# timer-LED.net
KiCad netlist of a schematic drawn in EAGLE
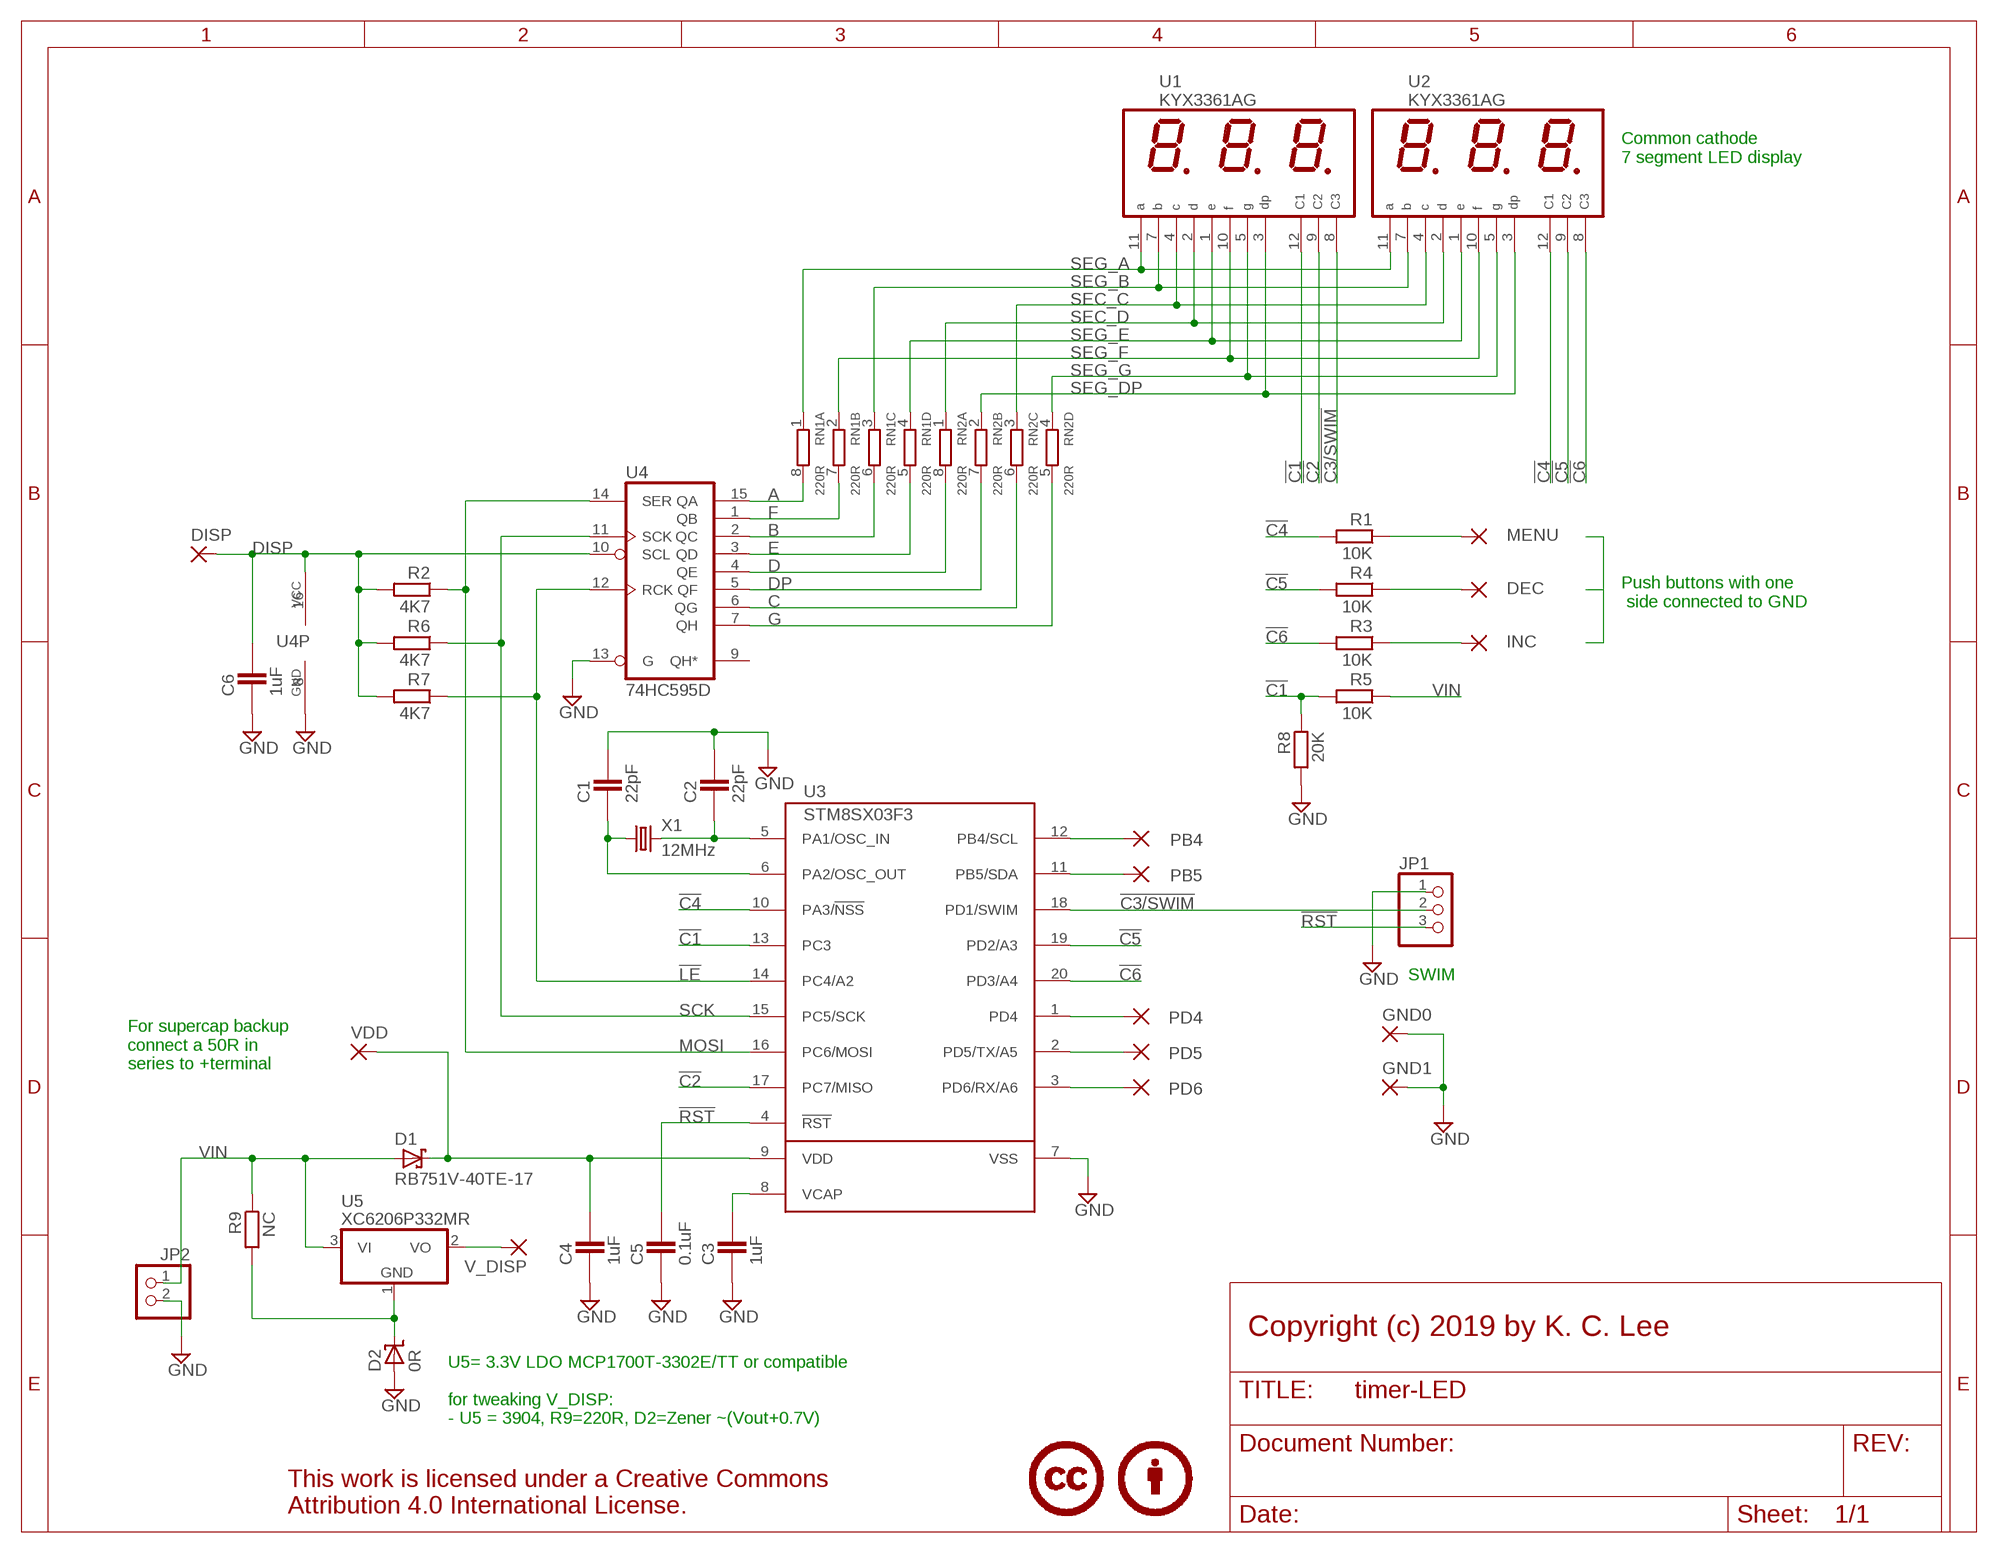
[diagram p0: schematic, sheet 1]

(export (version "E")
  (design (tool "Eeschema 10.0.6"))
  (components
    (comp (ref "C1")
      (value "22pF")
      (footprint "eagle-import:CAPC1608X92N")
      (libsource (lib "eagle-import") (part "CAPACITOR_0603"))
    )
    (comp (ref "C2")
      (value "22pF")
      (footprint "eagle-import:CAPC1608X92N")
      (libsource (lib "eagle-import") (part "CAPACITOR_0603"))
    )
    (comp (ref "C3")
      (value "1uF")
      (footprint "eagle-import:CAPC1608X92N")
      (libsource (lib "eagle-import") (part "CAPACITOR_0603"))
    )
    (comp (ref "C4")
      (value "1uF")
      (footprint "eagle-import:CAPC1608X92N")
      (libsource (lib "eagle-import") (part "CAPACITOR_0603"))
    )
    (comp (ref "C5")
      (value "0.1uF")
      (footprint "eagle-import:CAPC1608X92N")
      (libsource (lib "eagle-import") (part "CAPACITOR_0603"))
    )
    (comp (ref "C6")
      (value "1uF")
      (footprint "eagle-import:CAP2012X70N")
      (libsource (lib "eagle-import") (part "CAPACITOR_0805N"))
    )
    (comp (ref "D1")
      (value "RB751V-40TE-17")
      (footprint "eagle-import:SOD2514X100N")
      (libsource (lib "eagle-import") (part "SCHOTTKY_SOD-323"))
    )
    (comp (ref "D2")
      (value "0R")
      (footprint "eagle-import:SOD2514X100N")
      (libsource (lib "eagle-import") (part "ZENER_SOD-323"))
    )
    (comp (ref "DEC")
      (value "SMD2")
      (footprint "eagle-import:SMD1,27-2,54")
      (libsource (lib "eagle-import") (part "SMD2"))
    )
    (comp (ref "DISP")
      (value "SMD2")
      (footprint "eagle-import:SMD1,27-2,54")
      (libsource (lib "eagle-import") (part "SMD2"))
    )
    (comp (ref "GND0")
      (value "SMD2")
      (footprint "eagle-import:SMD1,27-2,54")
      (libsource (lib "eagle-import") (part "SMD2"))
    )
    (comp (ref "GND1")
      (value "SMD2")
      (footprint "eagle-import:SMD1,27-2,54")
      (libsource (lib "eagle-import") (part "SMD2"))
    )
    (comp (ref "INC")
      (value "SMD2")
      (footprint "eagle-import:SMD1,27-2,54")
      (libsource (lib "eagle-import") (part "SMD2"))
    )
    (comp (ref "JP1")
      (value "PINHD-1X3")
      (footprint "eagle-import:1X03")
      (libsource (lib "eagle-import") (part "PINHD-1X3"))
    )
    (comp (ref "JP2")
      (value "PINHD-1X2_2.54")
      (footprint "eagle-import:1X02")
      (libsource (lib "eagle-import") (part "PINHD-1X2_2.54"))
    )
    (comp (ref "LICENSE1")
      (value "CC-BY75%")
      (footprint "eagle-import:CC-BY-75")
      (libsource (lib "eagle-import") (part "CC-BY75%"))
    )
    (comp (ref "MENU")
      (value "SMD2")
      (footprint "eagle-import:SMD1,27-2,54")
      (libsource (lib "eagle-import") (part "SMD2"))
    )
    (comp (ref "PB4")
      (value "SMD2")
      (footprint "eagle-import:SMD1,27-2,54")
      (libsource (lib "eagle-import") (part "SMD2"))
    )
    (comp (ref "PB5")
      (value "SMD2")
      (footprint "eagle-import:SMD1,27-2,54")
      (libsource (lib "eagle-import") (part "SMD2"))
    )
    (comp (ref "PD4")
      (value "SMD2")
      (footprint "eagle-import:SMD1,27-2,54")
      (libsource (lib "eagle-import") (part "SMD2"))
    )
    (comp (ref "PD5")
      (value "SMD2")
      (footprint "eagle-import:SMD1,27-2,54")
      (libsource (lib "eagle-import") (part "SMD2"))
    )
    (comp (ref "PD6")
      (value "SMD2")
      (footprint "eagle-import:SMD1,27-2,54")
      (libsource (lib "eagle-import") (part "SMD2"))
    )
    (comp (ref "R1")
      (value "10K")
      (footprint "eagle-import:RESC1608X55N")
      (libsource (lib "eagle-import") (part "RESISTOR_0603"))
    )
    (comp (ref "R2")
      (value "4K7")
      (footprint "eagle-import:RESC1608X55N")
      (libsource (lib "eagle-import") (part "RESISTOR_0603"))
    )
    (comp (ref "R3")
      (value "10K")
      (footprint "eagle-import:RESC2012X70N")
      (libsource (lib "eagle-import") (part "RESISTOR_0805"))
    )
    (comp (ref "R4")
      (value "10K")
      (footprint "eagle-import:RESC2012X70N")
      (libsource (lib "eagle-import") (part "RESISTOR_0805"))
    )
    (comp (ref "R5")
      (value "10K")
      (footprint "eagle-import:RESC1608X55N")
      (libsource (lib "eagle-import") (part "RESISTOR_0603"))
    )
    (comp (ref "R6")
      (value "4K7")
      (footprint "eagle-import:RESC1608X55N")
      (libsource (lib "eagle-import") (part "RESISTOR_0603"))
    )
    (comp (ref "R7")
      (value "4K7")
      (footprint "eagle-import:RESC1608X55N")
      (libsource (lib "eagle-import") (part "RESISTOR_0603"))
    )
    (comp (ref "R8")
      (value "20K")
      (footprint "eagle-import:RESC1608X55N")
      (libsource (lib "eagle-import") (part "RESISTOR_0603"))
    )
    (comp (ref "R9")
      (value "NC")
      (footprint "eagle-import:RESC1608X55N")
      (libsource (lib "eagle-import") (part "RESISTOR_0603"))
    )
    (comp (ref "RN1")
      (value "220R")
      (footprint "eagle-import:CAT16")
      (libsource (lib "eagle-import") (part "4R-NCAT16"))
    )
    (comp (ref "RN2")
      (value "220R")
      (footprint "eagle-import:CAT16")
      (libsource (lib "eagle-import") (part "4R-NCAT16"))
    )
    (comp (ref "U1")
      (value "KYX3361AG")
      (footprint "eagle-import:KYX3361")
      (libsource (lib "eagle-import") (part "DISP-3CC"))
    )
    (comp (ref "U2")
      (value "KYX3361AG")
      (footprint "eagle-import:KYX3361")
      (libsource (lib "eagle-import") (part "DISP-3CC"))
    )
    (comp (ref "U3")
      (value "STM8SX03F3")
      (footprint "eagle-import:TSSOP20")
      (libsource (lib "eagle-import") (part "STM8SX03F3"))
    )
    (comp (ref "U4")
      (value "74HC595D")
      (footprint "eagle-import:SO16")
      (libsource (lib "eagle-import") (part "74595DLS"))
    )
    (comp (ref "U5")
      (value "XC6206P332MR")
      (footprint "eagle-import:SOT95P280X135-3N")
      (libsource (lib "eagle-import") (part "MCP1700/TT"))
    )
    (comp (ref "VDD")
      (value "SMD2")
      (footprint "eagle-import:SMD1,27-2,54")
      (libsource (lib "eagle-import") (part "SMD2"))
    )
    (comp (ref "V_DISP")
      (value "SMD2")
      (footprint "eagle-import:SMD1,27-2,54")
      (libsource (lib "eagle-import") (part "SMD2"))
    )
    (comp (ref "X1")
      (value "12MHz")
      (footprint "eagle-import:HC49U-V")
      (libsource (lib "eagle-import") (part "CRYSTALHC49U-V"))
    )
  )
  (nets
    (net (code "1") (name "/A") (class "Default")
      (node (ref "RN1") (pin "8") (pinfunction "2_8") (pintype "passive"))
      (node (ref "U4") (pin "15") (pinfunction "QA_15") (pintype "tri_state"))
    )
    (net (code "2") (name "/B") (class "Default")
      (node (ref "RN1") (pin "6") (pinfunction "2_6") (pintype "passive"))
      (node (ref "U4") (pin "2") (pinfunction "QC_2") (pintype "tri_state"))
    )
    (net (code "3") (name "/C") (class "Default")
      (node (ref "RN2") (pin "6") (pinfunction "2_6") (pintype "passive"))
      (node (ref "U4") (pin "6") (pinfunction "QG_6") (pintype "tri_state"))
    )
    (net (code "4") (name "/D") (class "Default")
      (node (ref "RN2") (pin "8") (pinfunction "2_8") (pintype "passive"))
      (node (ref "U4") (pin "4") (pinfunction "QE_4") (pintype "tri_state"))
    )
    (net (code "5") (name "/DISP") (class "Default")
      (node (ref "C6") (pin "2") (pinfunction "2_2") (pintype "passive"))
      (node (ref "DISP") (pin "1") (pinfunction "P_1") (pintype "passive"))
      (node (ref "R2") (pin "2") (pinfunction "2_2") (pintype "passive"))
      (node (ref "R6") (pin "2") (pinfunction "2_2") (pintype "passive"))
      (node (ref "R7") (pin "2") (pinfunction "2_2") (pintype "passive"))
      (node (ref "U4") (pin "10") (pinfunction "SCL_10") (pintype "input"))
      (node (ref "U4") (pin "16") (pinfunction "VCC_16") (pintype "power_in"))
    )
    (net (code "6") (name "/DP") (class "Default")
      (node (ref "RN2") (pin "7") (pinfunction "2_7") (pintype "passive"))
      (node (ref "U4") (pin "5") (pinfunction "QF_5") (pintype "tri_state"))
    )
    (net (code "7") (name "/E") (class "Default")
      (node (ref "RN1") (pin "5") (pinfunction "2_5") (pintype "passive"))
      (node (ref "U4") (pin "3") (pinfunction "QD_3") (pintype "tri_state"))
    )
    (net (code "8") (name "/F") (class "Default")
      (node (ref "RN1") (pin "7") (pinfunction "2_7") (pintype "passive"))
      (node (ref "U4") (pin "1") (pinfunction "QB_1") (pintype "tri_state"))
    )
    (net (code "9") (name "/G") (class "Default")
      (node (ref "RN2") (pin "5") (pinfunction "2_5") (pintype "passive"))
      (node (ref "U4") (pin "7") (pinfunction "QH_7") (pintype "tri_state"))
    )
    (net (code "10") (name "/MOSI") (class "Default")
      (node (ref "R2") (pin "1") (pinfunction "1_1") (pintype "passive"))
      (node (ref "U3") (pin "16") (pinfunction "PC6/MOSI_16") (pintype "bidirectional"))
      (node (ref "U4") (pin "14") (pinfunction "SER_14") (pintype "input"))
    )
    (net (code "11") (name "/SCK") (class "Default")
      (node (ref "R6") (pin "1") (pinfunction "1_1") (pintype "passive"))
      (node (ref "U3") (pin "15") (pinfunction "PC5/SCK_15") (pintype "bidirectional"))
      (node (ref "U4") (pin "11") (pinfunction "SCK_11") (pintype "input"))
    )
    (net (code "12") (name "/SEC_C") (class "Default")
      (node (ref "RN2") (pin "3") (pinfunction "1_3") (pintype "passive"))
      (node (ref "U1") (pin "4") (pinfunction "C_4") (pintype "passive"))
      (node (ref "U2") (pin "4") (pinfunction "C_4") (pintype "passive"))
    )
    (net (code "13") (name "/SEC_D") (class "Default")
      (node (ref "RN2") (pin "1") (pinfunction "1_1") (pintype "passive"))
      (node (ref "U1") (pin "2") (pinfunction "D_2") (pintype "passive"))
      (node (ref "U2") (pin "2") (pinfunction "D_2") (pintype "passive"))
    )
    (net (code "14") (name "/SEG_A") (class "Default")
      (node (ref "RN1") (pin "1") (pinfunction "1_1") (pintype "passive"))
      (node (ref "U1") (pin "11") (pinfunction "A_11") (pintype "passive"))
      (node (ref "U2") (pin "11") (pinfunction "A_11") (pintype "passive"))
    )
    (net (code "15") (name "/SEG_B") (class "Default")
      (node (ref "RN1") (pin "3") (pinfunction "1_3") (pintype "passive"))
      (node (ref "U1") (pin "7") (pinfunction "B_7") (pintype "passive"))
      (node (ref "U2") (pin "7") (pinfunction "B_7") (pintype "passive"))
    )
    (net (code "16") (name "/SEG_DP") (class "Default")
      (node (ref "RN2") (pin "2") (pinfunction "1_2") (pintype "passive"))
      (node (ref "U1") (pin "3") (pinfunction "DP_3") (pintype "passive"))
      (node (ref "U2") (pin "3") (pinfunction "DP_3") (pintype "passive"))
    )
    (net (code "17") (name "/SEG_E") (class "Default")
      (node (ref "RN1") (pin "4") (pinfunction "1_4") (pintype "passive"))
      (node (ref "U1") (pin "1") (pinfunction "E_1") (pintype "passive"))
      (node (ref "U2") (pin "1") (pinfunction "E_1") (pintype "passive"))
    )
    (net (code "18") (name "/SEG_F") (class "Default")
      (node (ref "RN1") (pin "2") (pinfunction "1_2") (pintype "passive"))
      (node (ref "U1") (pin "10") (pinfunction "F_10") (pintype "passive"))
      (node (ref "U2") (pin "10") (pinfunction "F_10") (pintype "passive"))
    )
    (net (code "19") (name "/SEG_G") (class "Default")
      (node (ref "RN2") (pin "4") (pinfunction "1_4") (pintype "passive"))
      (node (ref "U1") (pin "5") (pinfunction "G_5") (pintype "passive"))
      (node (ref "U2") (pin "5") (pinfunction "G_5") (pintype "passive"))
    )
    (net (code "20") (name "/VIN") (class "Default")
      (node (ref "D1") (pin "A") (pinfunction "A_A") (pintype "passive"))
      (node (ref "JP2") (pin "1") (pinfunction "1_1") (pintype "passive"))
      (node (ref "R5") (pin "1") (pinfunction "1_1") (pintype "passive"))
      (node (ref "R9") (pin "1") (pinfunction "1_1") (pintype "passive"))
      (node (ref "U5") (pin "3") (pinfunction "VI_3") (pintype "input"))
    )
    (net (code "21") (name "/~{C1}") (class "Default")
      (node (ref "R5") (pin "2") (pinfunction "2_2") (pintype "passive"))
      (node (ref "R8") (pin "1") (pinfunction "1_1") (pintype "passive"))
      (node (ref "U1") (pin "12") (pinfunction "C1_12") (pintype "passive"))
      (node (ref "U3") (pin "13") (pinfunction "PC3_13") (pintype "bidirectional"))
    )
    (net (code "22") (name "/~{C2}") (class "Default")
      (node (ref "U1") (pin "9") (pinfunction "C2_9") (pintype "passive"))
      (node (ref "U3") (pin "17") (pinfunction "PC7/MISO_17") (pintype "bidirectional"))
    )
    (net (code "23") (name "/~{C3{slash}SWIM}") (class "Default")
      (node (ref "JP1") (pin "2") (pinfunction "2_2") (pintype "passive"))
      (node (ref "U1") (pin "8") (pinfunction "C3_8") (pintype "passive"))
      (node (ref "U3") (pin "18") (pinfunction "PD1/SWIM_18") (pintype "input"))
    )
    (net (code "24") (name "/~{C4}") (class "Default")
      (node (ref "R1") (pin "2") (pinfunction "2_2") (pintype "passive"))
      (node (ref "U2") (pin "12") (pinfunction "C1_12") (pintype "passive"))
      (node (ref "U3") (pin "10") (pinfunction "PA3/~{NSS}_10") (pintype "bidirectional"))
    )
    (net (code "25") (name "/~{C5}") (class "Default")
      (node (ref "R4") (pin "2") (pinfunction "2_2") (pintype "passive"))
      (node (ref "U2") (pin "9") (pinfunction "C2_9") (pintype "passive"))
      (node (ref "U3") (pin "19") (pinfunction "PD2/A3_19") (pintype "bidirectional"))
    )
    (net (code "26") (name "/~{C6}") (class "Default")
      (node (ref "R3") (pin "2") (pinfunction "2_2") (pintype "passive"))
      (node (ref "U2") (pin "8") (pinfunction "C3_8") (pintype "passive"))
      (node (ref "U3") (pin "20") (pinfunction "PD3/A4_20") (pintype "bidirectional"))
    )
    (net (code "27") (name "/~{LE}") (class "Default")
      (node (ref "R7") (pin "1") (pinfunction "1_1") (pintype "passive"))
      (node (ref "U3") (pin "14") (pinfunction "PC4/A2_14") (pintype "bidirectional"))
      (node (ref "U4") (pin "12") (pinfunction "RCK_12") (pintype "input"))
    )
    (net (code "28") (name "/~{RST}") (class "Default")
      (node (ref "C5") (pin "2") (pinfunction "2_2") (pintype "passive"))
      (node (ref "JP1") (pin "3") (pinfunction "3_3") (pintype "passive"))
      (node (ref "U3") (pin "4") (pinfunction "~{RST}_4") (pintype "input"))
    )
    (net (code "29") (name "GND") (class "Default")
      (node (ref "C1") (pin "2") (pinfunction "2_2") (pintype "passive"))
      (node (ref "C2") (pin "2") (pinfunction "2_2") (pintype "passive"))
      (node (ref "C3") (pin "1") (pinfunction "1_1") (pintype "passive"))
      (node (ref "C4") (pin "1") (pinfunction "1_1") (pintype "passive"))
      (node (ref "C5") (pin "1") (pinfunction "1_1") (pintype "passive"))
      (node (ref "C6") (pin "1") (pinfunction "1_1") (pintype "passive"))
      (node (ref "D2") (pin "A") (pinfunction "A_A") (pintype "passive"))
      (node (ref "GND0") (pin "1") (pinfunction "P_1") (pintype "passive"))
      (node (ref "GND1") (pin "1") (pinfunction "P_1") (pintype "passive"))
      (node (ref "JP1") (pin "1") (pinfunction "1_1") (pintype "passive"))
      (node (ref "JP2") (pin "2") (pinfunction "2_2") (pintype "passive"))
      (node (ref "R8") (pin "2") (pinfunction "2_2") (pintype "passive"))
      (node (ref "U3") (pin "7") (pinfunction "VSS_7") (pintype "input"))
      (node (ref "U4") (pin "13") (pinfunction "G_13") (pintype "input"))
      (node (ref "U4") (pin "8") (pinfunction "GND_8") (pintype "power_in"))
    )
    (net (code "30") (name "Net-(DEC-P)") (class "Default")
      (node (ref "DEC") (pin "1") (pinfunction "P_1") (pintype "passive"))
      (node (ref "R4") (pin "1") (pinfunction "1_1") (pintype "passive"))
    )
    (net (code "31") (name "Net-(INC-P)") (class "Default")
      (node (ref "INC") (pin "1") (pinfunction "P_1") (pintype "passive"))
      (node (ref "R3") (pin "1") (pinfunction "1_1") (pintype "passive"))
    )
    (net (code "32") (name "Net-(MENU-P)") (class "Default")
      (node (ref "MENU") (pin "1") (pinfunction "P_1") (pintype "passive"))
      (node (ref "R1") (pin "1") (pinfunction "1_1") (pintype "passive"))
    )
    (net (code "33") (name "Net-(PB4-P)") (class "Default")
      (node (ref "PB4") (pin "1") (pinfunction "P_1") (pintype "passive"))
      (node (ref "U3") (pin "12") (pinfunction "PB4/SCL_12") (pintype "bidirectional"))
    )
    (net (code "34") (name "Net-(PB5-P)") (class "Default")
      (node (ref "PB5") (pin "1") (pinfunction "P_1") (pintype "passive"))
      (node (ref "U3") (pin "11") (pinfunction "PB5/SDA_11") (pintype "bidirectional"))
    )
    (net (code "35") (name "Net-(PD4-P)") (class "Default")
      (node (ref "PD4") (pin "1") (pinfunction "P_1") (pintype "passive"))
      (node (ref "U3") (pin "1") (pinfunction "PD4_1") (pintype "bidirectional"))
    )
    (net (code "36") (name "Net-(PD5-P)") (class "Default")
      (node (ref "PD5") (pin "1") (pinfunction "P_1") (pintype "passive"))
      (node (ref "U3") (pin "2") (pinfunction "PD5/TX/A5_2") (pintype "bidirectional"))
    )
    (net (code "37") (name "Net-(PD6-P)") (class "Default")
      (node (ref "PD6") (pin "1") (pinfunction "P_1") (pintype "passive"))
      (node (ref "U3") (pin "3") (pinfunction "PD6/RX/A6_3") (pintype "bidirectional"))
    )
    (net (code "38") (name "Net-(U3-PA1{slash}OSC_IN)") (class "Default")
      (node (ref "C2") (pin "1") (pinfunction "1_1") (pintype "passive"))
      (node (ref "U3") (pin "5") (pinfunction "PA1/OSC_IN_5") (pintype "input"))
      (node (ref "X1") (pin "2") (pinfunction "2_2") (pintype "passive"))
    )
    (net (code "39") (name "Net-(U3-PA2{slash}OSC_OUT)") (class "Default")
      (node (ref "C1") (pin "1") (pinfunction "1_1") (pintype "passive"))
      (node (ref "U3") (pin "6") (pinfunction "PA2/OSC_OUT_6") (pintype "output"))
      (node (ref "X1") (pin "1") (pinfunction "1_1") (pintype "passive"))
    )
    (net (code "40") (name "Net-(U3-VCAP)") (class "Default")
      (node (ref "C3") (pin "2") (pinfunction "2_2") (pintype "passive"))
      (node (ref "U3") (pin "8") (pinfunction "VCAP_8") (pintype "input"))
    )
    (net (code "41") (name "Net-(U3-VDD)") (class "Default")
      (node (ref "C4") (pin "2") (pinfunction "2_2") (pintype "passive"))
      (node (ref "D1") (pin "K") (pinfunction "K_K") (pintype "passive"))
      (node (ref "U3") (pin "9") (pinfunction "VDD_9") (pintype "input"))
      (node (ref "VDD") (pin "1") (pinfunction "P_1") (pintype "passive"))
    )
    (net (code "42") (name "Net-(U5-GND)") (class "Default")
      (node (ref "D2") (pin "K") (pinfunction "K_K") (pintype "passive"))
      (node (ref "R9") (pin "2") (pinfunction "2_2") (pintype "passive"))
      (node (ref "U5") (pin "1") (pinfunction "GND_1") (pintype "passive"))
    )
    (net (code "43") (name "Net-(U5-VO)") (class "Default")
      (node (ref "U5") (pin "2") (pinfunction "VO_2") (pintype "passive"))
      (node (ref "V_DISP") (pin "1") (pinfunction "P_1") (pintype "passive"))
    )
    (net (code "44") (name "unconnected-(U4A-QH*-Pad9)") (class "Default")
      (node (ref "U4") (pin "9") (pinfunction "QH*_9") (pintype "tri_state"))
    )
  )
)
